# MADcomboV2.net
KiCad netlist of a schematic drawn in EAGLE
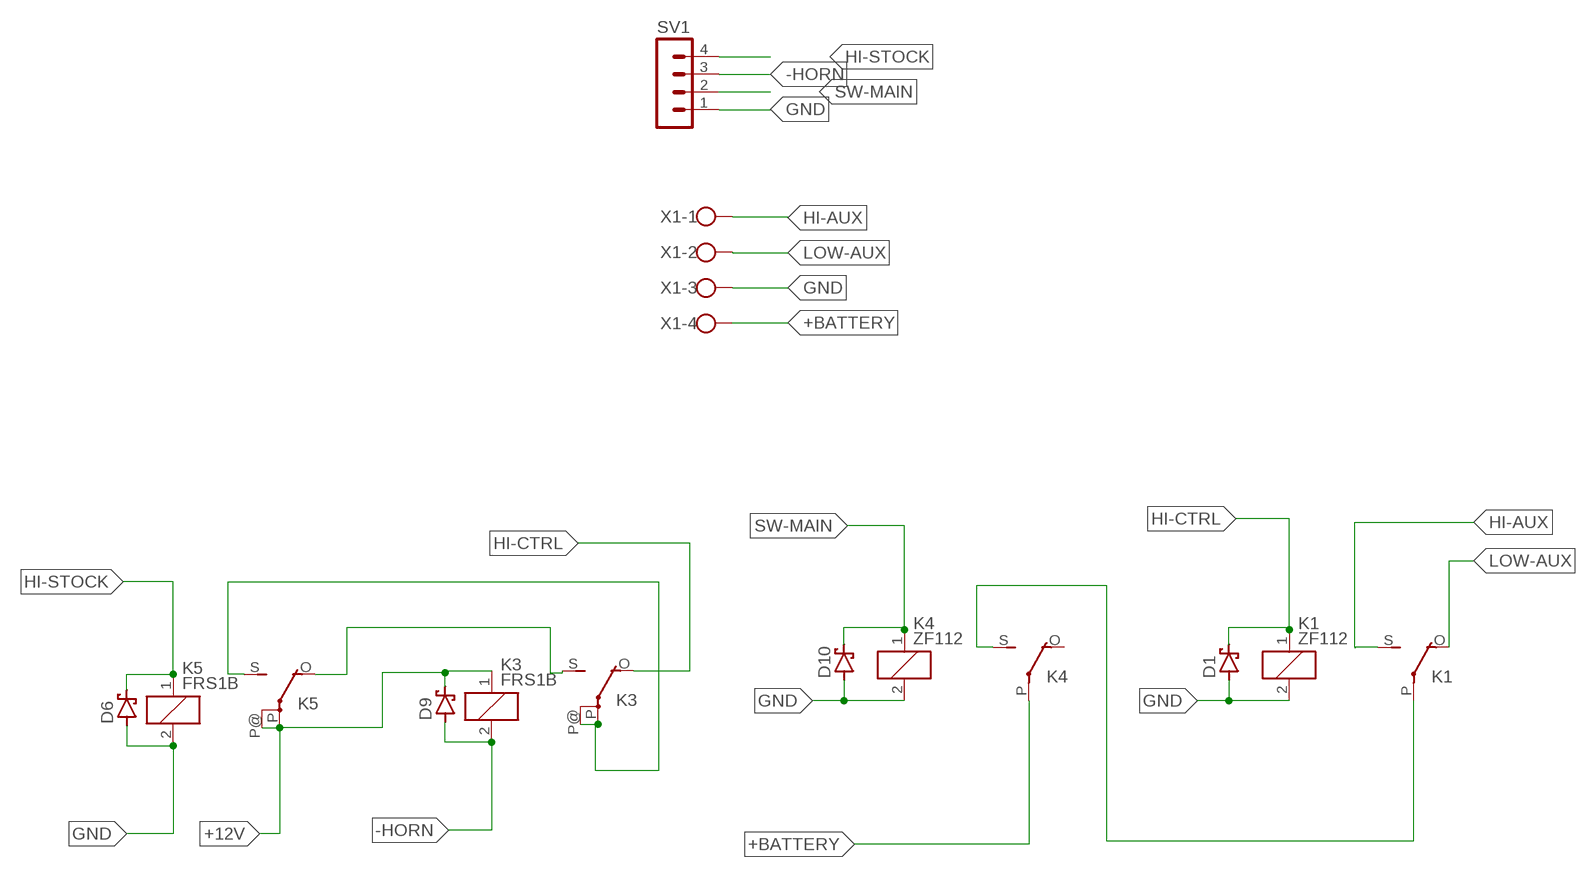
[diagram p0: schematic, sheet 1]

(export (version "E")
  (design (tool "Eeschema 10.0.6"))
  (components
    (comp (ref "D1")
      (value "SCHOTTKY-DIODESMD")
      (footprint "eagle-import:SMB")
      (libsource (lib "eagle-import") (part "SCHOTTKY-DIODESMD"))
    )
    (comp (ref "D6")
      (value "SCHOTTKY-DIODESMD")
      (footprint "eagle-import:SMB")
      (libsource (lib "eagle-import") (part "SCHOTTKY-DIODESMD"))
    )
    (comp (ref "D9")
      (value "SCHOTTKY-DIODESMD")
      (footprint "eagle-import:SMB")
      (libsource (lib "eagle-import") (part "SCHOTTKY-DIODESMD"))
    )
    (comp (ref "D10")
      (value "SCHOTTKY-DIODESMD")
      (footprint "eagle-import:SMB")
      (libsource (lib "eagle-import") (part "SCHOTTKY-DIODESMD"))
    )
    (comp (ref "K1")
      (value "ZF112")
      (footprint "eagle-import:ZF112")
      (libsource (lib "eagle-import") (part "ZF112"))
    )
    (comp (ref "K3")
      (value "FRS1B")
      (footprint "eagle-import:FRS1B")
      (libsource (lib "eagle-import") (part "FRS1B"))
    )
    (comp (ref "K4")
      (value "ZF112")
      (footprint "eagle-import:ZF112")
      (libsource (lib "eagle-import") (part "ZF112"))
    )
    (comp (ref "K5")
      (value "FRS1B")
      (footprint "eagle-import:FRS1B")
      (libsource (lib "eagle-import") (part "FRS1B"))
    )
    (comp (ref "SV1")
      (value "MA04-1")
      (footprint "eagle-import:MA04-1")
      (libsource (lib "eagle-import") (part "MA04-1"))
    )
    (comp (ref "X1")
      (value "W237-4")
      (footprint "eagle-import:W237-4")
      (libsource (lib "eagle-import") (part "W237-4"))
    )
  )
  (nets
    (net (code "1") (name "+12V") (class "Default")
      (node (ref "D9") (pin "C") (pinfunction "C_C") (pintype "passive"))
      (node (ref "K3") (pin "1") (pinfunction "1_1") (pintype "passive"))
      (node (ref "K5") (pin "P") (pinfunction "P_P") (pintype "passive"))
      (node (ref "K5") (pin "P@") (pinfunction "P_P@") (pintype "passive"))
    )
    (net (code "2") (name "+BATTERY") (class "Default")
      (node (ref "K4") (pin "P") (pinfunction "P_P") (pintype "passive"))
      (node (ref "X1") (pin "4") (pinfunction "KL_4") (pintype "passive"))
    )
    (net (code "3") (name "-HORN") (class "Default")
      (node (ref "D9") (pin "A") (pinfunction "A_A") (pintype "passive"))
      (node (ref "K3") (pin "2") (pinfunction "2_2") (pintype "passive"))
      (node (ref "SV1") (pin "3") (pinfunction "3_3") (pintype "passive"))
    )
    (net (code "4") (name "GND") (class "Default")
      (node (ref "D1") (pin "A") (pinfunction "A_A") (pintype "passive"))
      (node (ref "D10") (pin "A") (pinfunction "A_A") (pintype "passive"))
      (node (ref "D6") (pin "A") (pinfunction "A_A") (pintype "passive"))
      (node (ref "K1") (pin "2") (pinfunction "2_2") (pintype "passive"))
      (node (ref "K4") (pin "2") (pinfunction "2_2") (pintype "passive"))
      (node (ref "K5") (pin "2") (pinfunction "2_2") (pintype "passive"))
      (node (ref "SV1") (pin "1") (pinfunction "1_1") (pintype "passive"))
      (node (ref "X1") (pin "3") (pinfunction "KL_3") (pintype "passive"))
    )
    (net (code "5") (name "HI-AUX") (class "Default")
      (node (ref "K1") (pin "S") (pinfunction "S_S") (pintype "passive"))
      (node (ref "X1") (pin "1") (pinfunction "KL_1") (pintype "passive"))
    )
    (net (code "6") (name "HI-CTRL") (class "Default")
      (node (ref "D1") (pin "C") (pinfunction "C_C") (pintype "passive"))
      (node (ref "K1") (pin "1") (pinfunction "1_1") (pintype "passive"))
      (node (ref "K3") (pin "O") (pinfunction "O_O") (pintype "passive"))
    )
    (net (code "7") (name "HI-STOCK") (class "Default")
      (node (ref "D6") (pin "C") (pinfunction "C_C") (pintype "passive"))
      (node (ref "K5") (pin "1") (pinfunction "1_1") (pintype "passive"))
      (node (ref "SV1") (pin "4") (pinfunction "4_4") (pintype "passive"))
    )
    (net (code "8") (name "LOW-AUX") (class "Default")
      (node (ref "K1") (pin "O") (pinfunction "O_O") (pintype "passive"))
      (node (ref "X1") (pin "2") (pinfunction "KL_2") (pintype "passive"))
    )
    (net (code "9") (name "Net-(K1-PadP)") (class "Default")
      (node (ref "K1") (pin "P") (pinfunction "P_P") (pintype "passive"))
      (node (ref "K4") (pin "S") (pinfunction "S_S") (pintype "passive"))
    )
    (net (code "10") (name "Net-(K3-PadP)") (class "Default")
      (node (ref "K3") (pin "P") (pinfunction "P_P") (pintype "passive"))
      (node (ref "K3") (pin "P@") (pinfunction "P_P@") (pintype "passive"))
      (node (ref "K5") (pin "S") (pinfunction "S_S") (pintype "passive"))
    )
    (net (code "11") (name "Net-(K3-PadS)") (class "Default")
      (node (ref "K3") (pin "S") (pinfunction "S_S") (pintype "passive"))
      (node (ref "K5") (pin "O") (pinfunction "O_O") (pintype "passive"))
    )
    (net (code "12") (name "SW-MAIN") (class "Default")
      (node (ref "D10") (pin "C") (pinfunction "C_C") (pintype "passive"))
      (node (ref "K4") (pin "1") (pinfunction "1_1") (pintype "passive"))
      (node (ref "SV1") (pin "2") (pinfunction "2_2") (pintype "passive"))
    )
    (net (code "13") (name "unconnected-(K4-PadO)") (class "Default")
      (node (ref "K4") (pin "O") (pinfunction "O_O") (pintype "passive"))
    )
  )
)
